# PWR_BUCK.net
KiCad netlist of a schematic drawn in Altium Designer
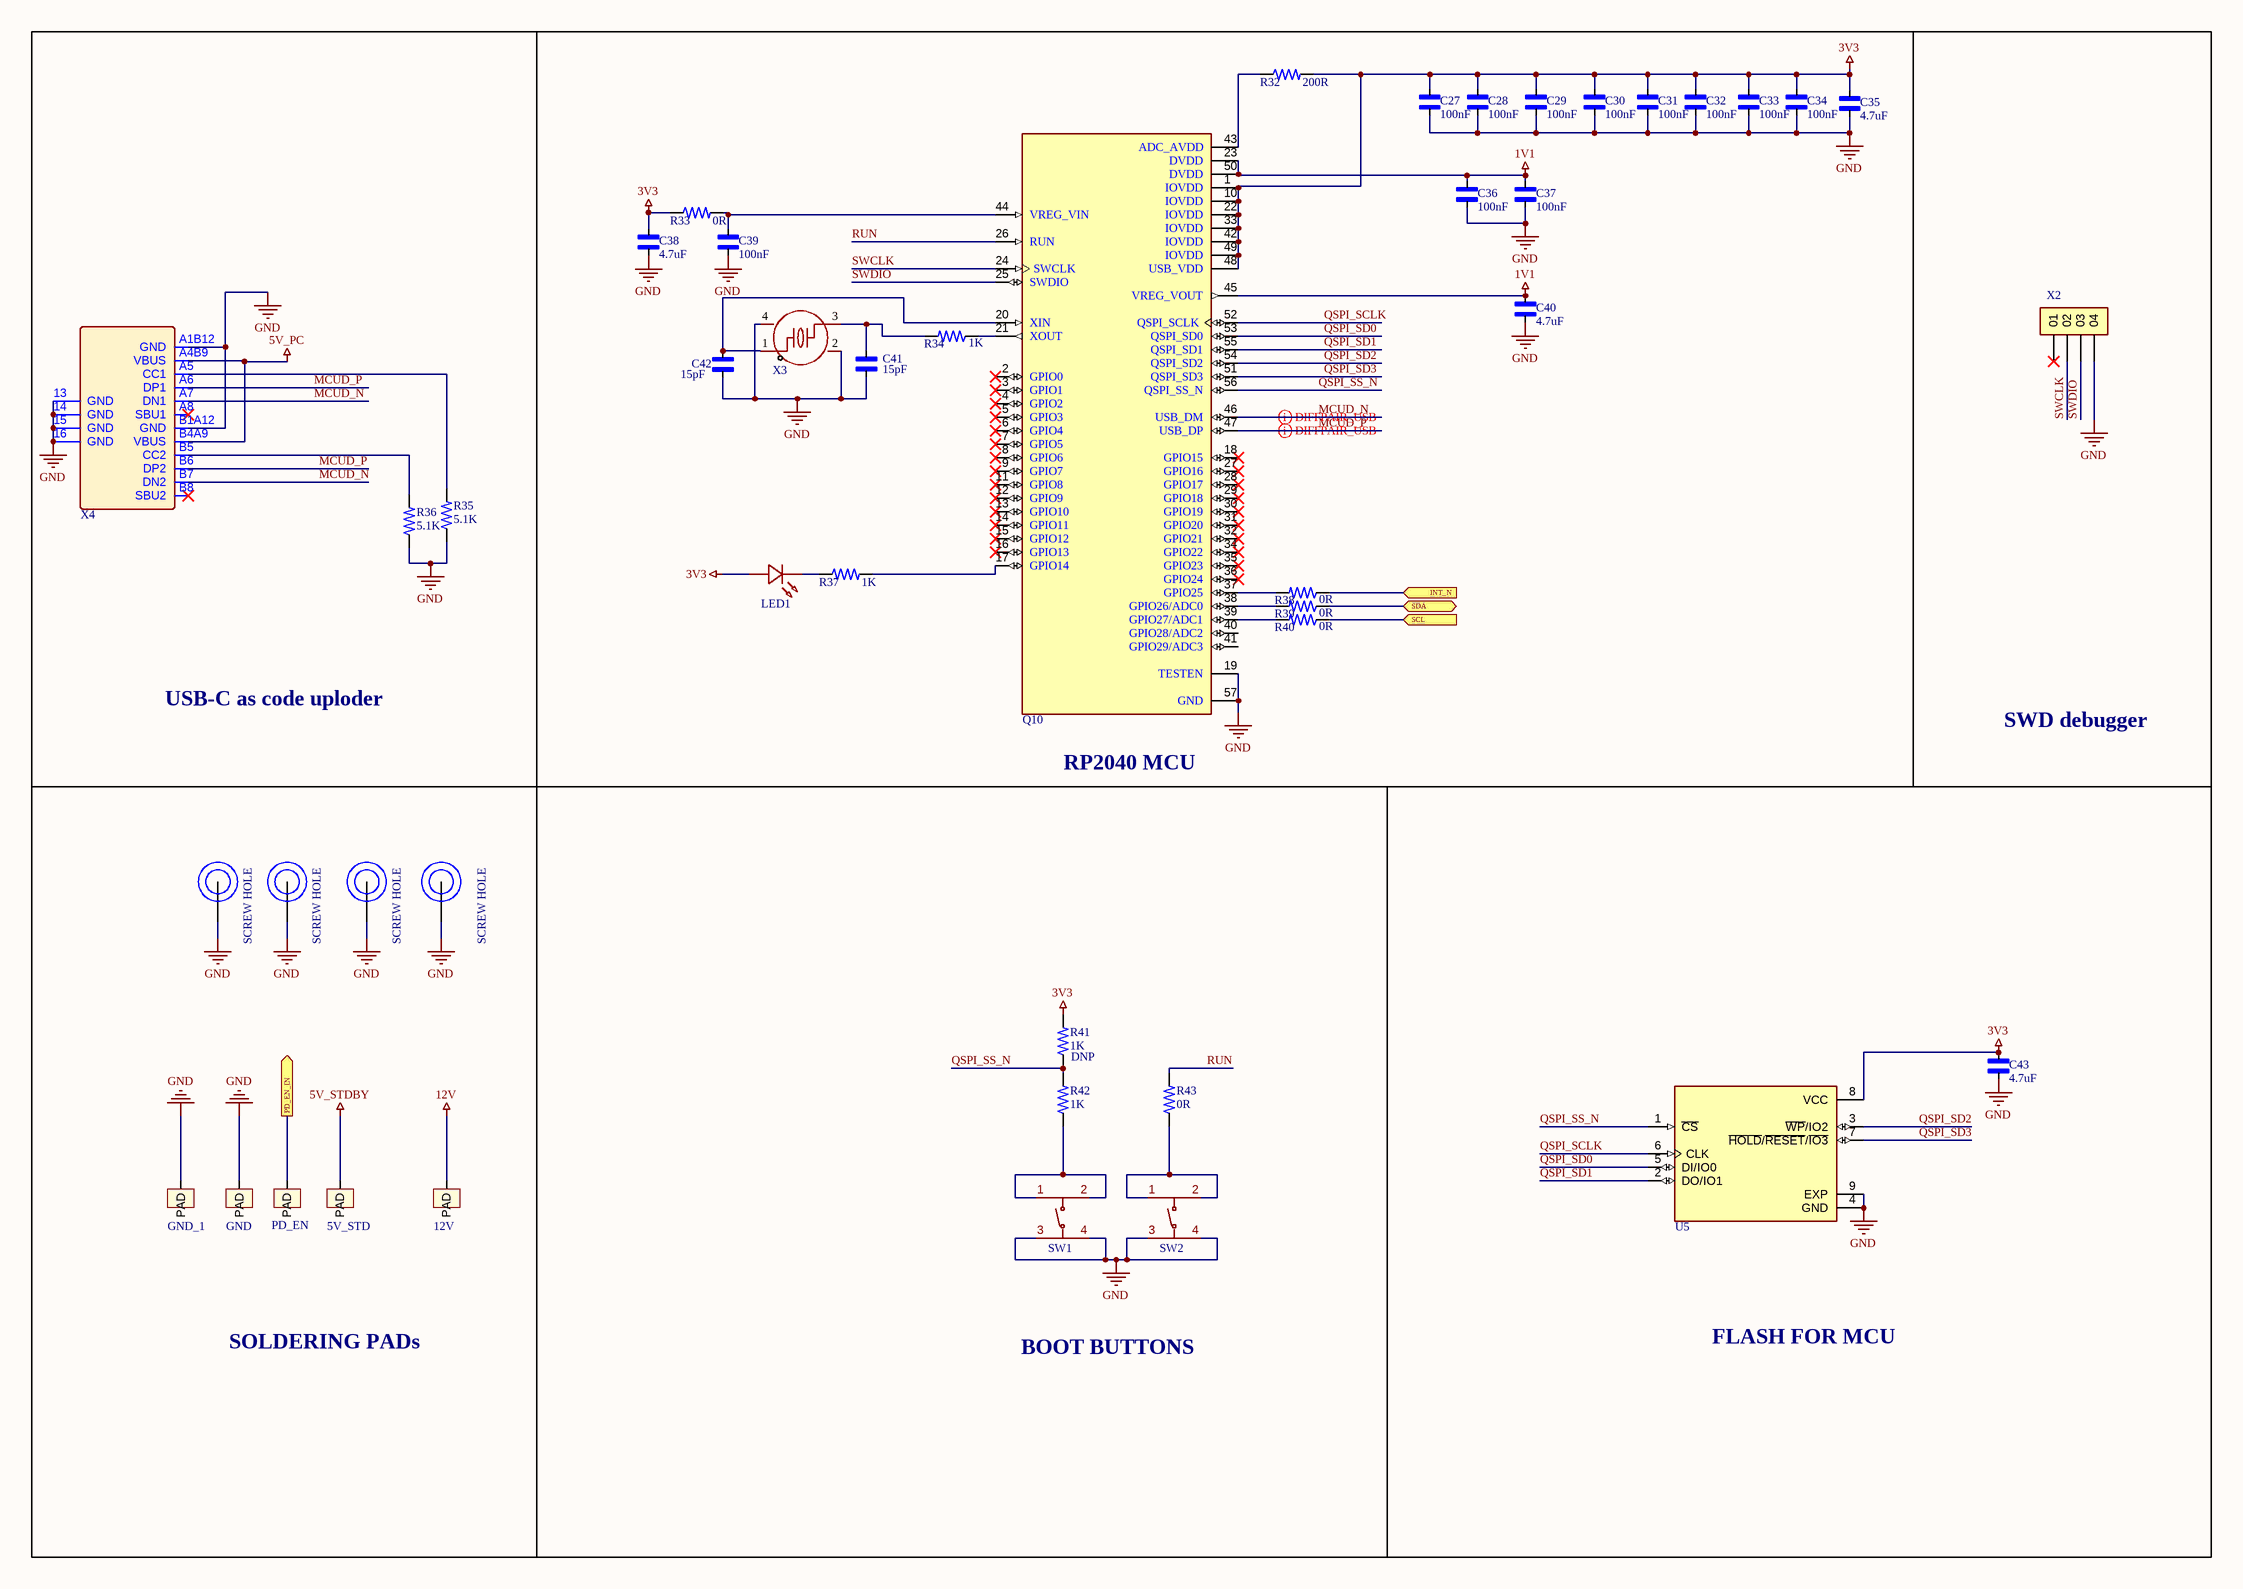
[diagram p0: PWR_BUCK.SchDoc]

(export (version "E")
  (design (tool "Eeschema 10.0.6"))
  (components
    (comp (ref "5V_STD")
      (value "solder pad")
      (footprint "1mm hole")
      (libsource (lib "USB_PD_PSU") (part "solder pad"))
    )
    (comp (ref "12V")
      (value "solder pad")
      (footprint "14 awg")
      (libsource (lib "USB_PD_PSU") (part "solder pad"))
    )
    (comp (ref "C27")
      (value "100nF")
      (footprint "CAP_0603")
      (description "SMD Capacitor")
      (fields (field (name "TOLERANCE") "±10%") (field (name "Comment") "SMD capacitor"))
      (libsource (lib "USB_PD_PSU") (part "CAP_SMD_CERAMIC"))
    )
    (comp (ref "C28")
      (value "100nF")
      (footprint "CAP_0603")
      (description "SMD Capacitor")
      (fields (field (name "TOLERANCE") "±10%") (field (name "Comment") "SMD capacitor"))
      (libsource (lib "USB_PD_PSU") (part "CAP_SMD_CERAMIC"))
    )
    (comp (ref "C29")
      (value "100nF")
      (footprint "CAP_0603")
      (description "SMD Capacitor")
      (fields (field (name "TOLERANCE") "±10%") (field (name "Comment") "SMD capacitor"))
      (libsource (lib "USB_PD_PSU") (part "CAP_SMD_CERAMIC"))
    )
    (comp (ref "C30")
      (value "100nF")
      (footprint "CAP_0603")
      (description "SMD Capacitor")
      (fields (field (name "TOLERANCE") "±10%") (field (name "Comment") "SMD capacitor"))
      (libsource (lib "USB_PD_PSU") (part "CAP_SMD_CERAMIC"))
    )
    (comp (ref "C31")
      (value "100nF")
      (footprint "CAP_0603")
      (description "SMD Capacitor")
      (fields (field (name "TOLERANCE") "±10%") (field (name "Comment") "SMD capacitor"))
      (libsource (lib "USB_PD_PSU") (part "CAP_SMD_CERAMIC"))
    )
    (comp (ref "C32")
      (value "100nF")
      (footprint "CAP_0603")
      (description "SMD Capacitor")
      (fields (field (name "TOLERANCE") "±10%") (field (name "Comment") "SMD capacitor"))
      (libsource (lib "USB_PD_PSU") (part "CAP_SMD_CERAMIC"))
    )
    (comp (ref "C33")
      (value "100nF")
      (footprint "CAP_0603")
      (description "SMD Capacitor")
      (fields (field (name "TOLERANCE") "±10%") (field (name "Comment") "SMD capacitor"))
      (libsource (lib "USB_PD_PSU") (part "CAP_SMD_CERAMIC"))
    )
    (comp (ref "C34")
      (value "100nF")
      (footprint "CAP_0603")
      (description "SMD Capacitor")
      (fields (field (name "TOLERANCE") "±10%") (field (name "Comment") "SMD capacitor"))
      (libsource (lib "USB_PD_PSU") (part "CAP_SMD_CERAMIC"))
    )
    (comp (ref "C35")
      (value "4.7uF")
      (footprint "CAP_0603")
      (description "SMD Capacitor")
      (fields (field (name "TOLERANCE") "±10%") (field (name "Comment") "SMD capacitor"))
      (libsource (lib "USB_PD_PSU") (part "CAP_SMD_CERAMIC"))
    )
    (comp (ref "C36")
      (value "100nF")
      (footprint "CAP_0603")
      (description "SMD Capacitor")
      (fields (field (name "TOLERANCE") "±10%") (field (name "Comment") "SMD capacitor"))
      (libsource (lib "USB_PD_PSU") (part "CAP_SMD_CERAMIC"))
    )
    (comp (ref "C37")
      (value "100nF")
      (footprint "CAP_0603")
      (description "SMD Capacitor")
      (fields (field (name "TOLERANCE") "±10%") (field (name "Comment") "SMD capacitor"))
      (libsource (lib "USB_PD_PSU") (part "CAP_SMD_CERAMIC"))
    )
    (comp (ref "C38")
      (value "4.7uF")
      (footprint "CAP_0603")
      (description "SMD Capacitor")
      (fields (field (name "TOLERANCE") "±10%") (field (name "Comment") "SMD capacitor"))
      (libsource (lib "USB_PD_PSU") (part "CAP_SMD_CERAMIC"))
    )
    (comp (ref "C39")
      (value "100nF")
      (footprint "CAP_0603")
      (description "SMD Capacitor")
      (fields (field (name "TOLERANCE") "±10%") (field (name "Comment") "SMD capacitor"))
      (libsource (lib "USB_PD_PSU") (part "CAP_SMD_CERAMIC"))
    )
    (comp (ref "C40")
      (value "4.7uF")
      (footprint "CAP_0603")
      (description "SMD Capacitor")
      (fields (field (name "TOLERANCE") "±10%") (field (name "Comment") "SMD capacitor"))
      (libsource (lib "USB_PD_PSU") (part "CAP_SMD_CERAMIC"))
    )
    (comp (ref "C41")
      (value "15pF")
      (footprint "CAP_0603")
      (description "SMD Capacitor")
      (fields (field (name "TOLERANCE") "±10%") (field (name "Comment") "SMD capacitor"))
      (libsource (lib "") (part "CAP_SMD_CERAMIC_1"))
    )
    (comp (ref "C42")
      (value "15pF")
      (footprint "CAP_0603")
      (description "SMD Capacitor")
      (fields (field (name "TOLERANCE") "±10%") (field (name "Comment") "SMD capacitor"))
      (libsource (lib "") (part "CAP_SMD_CERAMIC_1"))
    )
    (comp (ref "C43")
      (value "4.7uF")
      (footprint "CAP_0603")
      (description "SMD Capacitor")
      (fields (field (name "TOLERANCE") "±10%") (field (name "Comment") "SMD capacitor"))
      (libsource (lib "USB_PD_PSU") (part "CAP_SMD_CERAMIC"))
    )
    (comp (ref "GND")
      (value "solder pad")
      (footprint "14 awg")
      (libsource (lib "USB_PD_PSU") (part "solder pad"))
    )
    (comp (ref "GND_1")
      (value "solder pad")
      (footprint "1mm hole")
      (libsource (lib "USB_PD_PSU") (part "solder pad"))
    )
    (comp (ref "LED1")
      (value "LED")
      (footprint "LED0603-RD_RED")
      (description "LED  SMD")
      (fields (field (name "MANIFACTURING PART NUMBER") "SZYY0603O"))
      (libsource (lib "USB_PD_PSU") (part "LED SMD"))
    )
    (comp (ref "PD_EN")
      (value "solder pad")
      (footprint "1mm hole")
      (libsource (lib "USB_PD_PSU") (part "solder pad"))
    )
    (comp (ref "Q10")
      (value "IC MCU 32BIT EXT MEM 56QFN")
      (footprint "QFN40P700X700X90-57N")
      (description "ARM® Cortex®-M0+ - Microcontroller IC 32-Bit Dual-Core 133MHz External Program Memory 56-QFN (7x7)")
      (fields (field (name "MANIFACTURING PART NUMBER") "RP2040") (field (name "JLCPCB PART #") "C2040"))
      (libsource (lib "USB_PD_PSU") (part "RP2040"))
    )
    (comp (ref "R32")
      (value "200R")
      (footprint "RES_0603")
      (description "SMD Resistor")
      (fields (field (name "TOLERANCE") "±5%"))
      (libsource (lib "USB_PD_PSU") (part "RES_SMD_CERAMIC"))
    )
    (comp (ref "R33")
      (value "0R")
      (footprint "RES_0603")
      (description "SMD Resistor")
      (fields (field (name "TOLERANCE") "±5%"))
      (libsource (lib "USB_PD_PSU") (part "RES_SMD_CERAMIC"))
    )
    (comp (ref "R34")
      (value "1K")
      (footprint "RES_0603")
      (description "SMD Resistor")
      (fields (field (name "TOLERANCE") "±5%") (field (name "Comment") "SMD resistor"))
      (libsource (lib "USB_PD_PSU") (part "RES_SMD_CERAMIC"))
    )
    (comp (ref "R35")
      (value "5.1K")
      (footprint "RES_0603")
      (description "SMD Resistor")
      (fields (field (name "TOLERANCE") "±5%") (field (name "Comment") "SMD resistor"))
      (libsource (lib "USB_PD_PSU") (part "RES_SMD_CERAMIC"))
    )
    (comp (ref "R36")
      (value "5.1K")
      (footprint "RES_0603")
      (description "SMD Resistor")
      (fields (field (name "TOLERANCE") "±5%") (field (name "Comment") "SMD resistor"))
      (libsource (lib "USB_PD_PSU") (part "RES_SMD_CERAMIC"))
    )
    (comp (ref "R37")
      (value "1K")
      (footprint "RES_0603")
      (description "SMD Resistor")
      (fields (field (name "TOLERANCE") "±5%"))
      (libsource (lib "USB_PD_PSU") (part "RES_SMD_CERAMIC"))
    )
    (comp (ref "R38")
      (value "0R")
      (footprint "RES_0603")
      (description "SMD Resistor")
      (fields (field (name "TOLERANCE") "±5%") (field (name "Comment") "SMD resistor"))
      (libsource (lib "USB_PD_PSU") (part "RES_SMD_CERAMIC"))
    )
    (comp (ref "R39")
      (value "0R")
      (footprint "RES_0603")
      (description "SMD Resistor")
      (fields (field (name "TOLERANCE") "±5%") (field (name "Comment") "SMD resistor"))
      (libsource (lib "USB_PD_PSU") (part "RES_SMD_CERAMIC"))
    )
    (comp (ref "R40")
      (value "0R")
      (footprint "RES_0603")
      (description "SMD Resistor")
      (fields (field (name "TOLERANCE") "±5%") (field (name "Comment") "SMD resistor"))
      (libsource (lib "USB_PD_PSU") (part "RES_SMD_CERAMIC"))
    )
    (comp (ref "R41")
      (value "DNP")
      (footprint "RES_0603")
      (description "SMD Resistor")
      (fields (field (name "TOLERANCE") "±5%") (field (name "ALTIUM_VALUE") "1K"))
      (libsource (lib "USB_PD_PSU") (part "RES_SMD_CERAMIC"))
    )
    (comp (ref "R42")
      (value "1K")
      (footprint "RES_0603")
      (description "SMD Resistor")
      (fields (field (name "TOLERANCE") "±5%") (field (name "Comment") "SMD resistor"))
      (libsource (lib "USB_PD_PSU") (part "RES_SMD_CERAMIC"))
    )
    (comp (ref "R43")
      (value "0R")
      (footprint "RES_0603")
      (description "SMD Resistor")
      (fields (field (name "TOLERANCE") "±5%") (field (name "Comment") "SMD resistor"))
      (libsource (lib "USB_PD_PSU") (part "RES_SMD_CERAMIC"))
    )
    (comp (ref "SH1")
      (value "SCREW HOLE")
      (footprint "PCB hole")
      (libsource (lib "USB_PD_PSU") (part "Hole"))
    )
    (comp (ref "SH2")
      (value "SCREW HOLE")
      (footprint "PCB hole")
      (libsource (lib "USB_PD_PSU") (part "Hole"))
    )
    (comp (ref "SH3")
      (value "SCREW HOLE")
      (footprint "PCB hole")
      (libsource (lib "USB_PD_PSU") (part "Hole"))
    )
    (comp (ref "SH4")
      (value "SCREW HOLE")
      (footprint "PCB hole")
      (libsource (lib "USB_PD_PSU") (part "Hole"))
    )
    (comp (ref "SW1")
      (value "Dev  Switch")
      (footprint "SW-SMD_4P-L4.2-W3.3-P2.15-LS5.1")
      (description "50mA Brick nogging SPST 12V SMD,3.3x4.2mm Tactile Switches ROHS")
      (fields (field (name "MANIFACTURING PART NUMBER") "TS-1089S-02526") (field (name "TOLERANCE") "±5%"))
      (libsource (lib "USB_PD_PSU") (part "TS-1089S-02526"))
    )
    (comp (ref "SW2")
      (value "Dev  Switch")
      (footprint "SW-SMD_4P-L4.2-W3.3-P2.15-LS5.1")
      (description "50mA Brick nogging SPST 12V SMD,3.3x4.2mm Tactile Switches ROHS")
      (fields (field (name "MANIFACTURING PART NUMBER") "TS-1089S-02526") (field (name "TOLERANCE") "±5%"))
      (libsource (lib "USB_PD_PSU") (part "TS-1089S-02526"))
    )
    (comp (ref "U5")
      (value "SPI Flash")
      (footprint "IC_W25Q16JVUXIQ_TR")
      (description "16Mbit 2.7V~3.6V 133MHz SPI USON-8-EP(2x3) Memory (ICs) ROHS")
      (fields
        (field (name "MANIFACTURING PART NUMBER") "W25Q16JVUXIQ")
        (field (name "JLCPCB PART #") "C2843335")
      )
      (libsource (lib "USB_PD_PSU") (part "W25Q16JVUXIQ"))
    )
    (comp (ref "X2")
      (value "Header X 5")
      (footprint "SAMTEC_TS-104-T-A")
      (description "4 pin header pitch 2.54mm")
      (fields
        (field (name "MANIFACTURING PART NUMBER") "2541WV-04P")
        (field (name "JLCPCB PART #") "C5383113")
      )
      (libsource (lib "USB_PD_PSU") (part "4 Pin Header"))
    )
    (comp (ref "X3")
      (value "Crystals")
      (footprint "CRYSTAL-SMD_4P-L3.2-W2.5-BL")
      (description "12 MHz ±30ppm Crystal 10pF 50 Ohms 4-SMD, No Lead")
      (fields (field (name "MANIFACTURING PART NUMBER") "ABM8-272-T3") (field (name "TOLERANCE") "±30ppm"))
      (libsource (lib "USB_PD_PSU") (part "ABM8-272-T3"))
    )
    (comp (ref "X4")
      (value "USB-C connector")
      (footprint "USB-C-SMD_TYPEC-304J-BCP16")
      (description "5A USB 3.1 1 Surface Mount, Right Angle 16P Female -40℃~+85℃ Type-C SMD USB Connectors ROHS")
      (fields
        (field (name "MANIFACTURING PART NUMBER") "TYPEC-304J-BCP16")
        (field (name "JLCPCB PART #") "C2835315")
      )
      (libsource (lib "USB_PD_PSU") (part "TYPEC-304J-BCP16"))
    )
  )
  (nets
    (net (code "1") (name "/INT_N") (class "Default")
      (node (ref "R38") (pin "1") (pinfunction "1_1") (pintype "passive"))
    )
    (net (code "2") (name "/MCUD_N") (class "Default")
      (node (ref "Q10") (pin "46") (pinfunction "USB_DM_46") (pintype "bidirectional"))
      (node (ref "X4") (pin "A7") (pinfunction "DN1_A7") (pintype "passive"))
      (node (ref "X4") (pin "B7") (pinfunction "DN2_B7") (pintype "passive"))
    )
    (net (code "3") (name "/MCUD_P") (class "Default")
      (node (ref "Q10") (pin "47") (pinfunction "USB_DP_47") (pintype "bidirectional"))
      (node (ref "X4") (pin "A6") (pinfunction "DP1_A6") (pintype "passive"))
      (node (ref "X4") (pin "B6") (pinfunction "DP2_B6") (pintype "passive"))
    )
    (net (code "4") (name "/PD_EN_IN") (class "Default")
      (node (ref "PD_EN") (pin "1") (pinfunction "PAD_1") (pintype "passive"))
    )
    (net (code "5") (name "/QSPI_SCLK") (class "Default")
      (node (ref "Q10") (pin "52") (pinfunction "QSPI_SCLK_52") (pintype "bidirectional"))
      (node (ref "U5") (pin "6") (pinfunction "CLK_6") (pintype "input"))
    )
    (net (code "6") (name "/QSPI_SD0") (class "Default")
      (node (ref "Q10") (pin "53") (pinfunction "QSPI_SD0_53") (pintype "bidirectional"))
      (node (ref "U5") (pin "5") (pinfunction "DI/IO0_5") (pintype "bidirectional"))
    )
    (net (code "7") (name "/QSPI_SD1") (class "Default")
      (node (ref "Q10") (pin "55") (pinfunction "QSPI_SD1_55") (pintype "bidirectional"))
      (node (ref "U5") (pin "2") (pinfunction "DO/IO1_2") (pintype "bidirectional"))
    )
    (net (code "8") (name "/QSPI_SD2") (class "Default")
      (node (ref "Q10") (pin "54") (pinfunction "QSPI_SD2_54") (pintype "bidirectional"))
      (node (ref "U5") (pin "3") (pinfunction "~{WP}/IO2_3") (pintype "bidirectional"))
    )
    (net (code "9") (name "/QSPI_SD3") (class "Default")
      (node (ref "Q10") (pin "51") (pinfunction "QSPI_SD3_51") (pintype "bidirectional"))
      (node (ref "U5") (pin "7") (pinfunction "~{HOLD}/~{RESET}/~{IO3}_7") (pintype "bidirectional"))
    )
    (net (code "10") (name "/QSPI_SS_N") (class "Default")
      (node (ref "Q10") (pin "56") (pinfunction "QSPI_SS_N_56") (pintype "bidirectional"))
      (node (ref "R41") (pin "1") (pinfunction "1_1") (pintype "passive"))
      (node (ref "R42") (pin "2") (pinfunction "2_2") (pintype "passive"))
      (node (ref "U5") (pin "1") (pinfunction "~{CS}_1") (pintype "input"))
    )
    (net (code "11") (name "/RUN") (class "Default")
      (node (ref "Q10") (pin "26") (pinfunction "RUN_26") (pintype "input"))
      (node (ref "R43") (pin "2") (pinfunction "2_2") (pintype "passive"))
    )
    (net (code "12") (name "/SCL") (class "Default")
      (node (ref "R40") (pin "1") (pinfunction "1_1") (pintype "passive"))
    )
    (net (code "13") (name "/SDA") (class "Default")
      (node (ref "R39") (pin "1") (pinfunction "1_1") (pintype "passive"))
    )
    (net (code "14") (name "/SWCLK") (class "Default")
      (node (ref "Q10") (pin "24") (pinfunction "SWCLK_24") (pintype "input"))
      (node (ref "X2") (pin "02") (pinfunction "02_02") (pintype "passive"))
    )
    (net (code "15") (name "/SWDIO") (class "Default")
      (node (ref "Q10") (pin "25") (pinfunction "SWDIO_25") (pintype "bidirectional"))
      (node (ref "X2") (pin "03") (pinfunction "03_03") (pintype "passive"))
    )
    (net (code "16") (name "1V1") (class "Default")
      (node (ref "C36") (pin "1") (pinfunction "1_1") (pintype "passive"))
      (node (ref "C37") (pin "1") (pinfunction "1_1") (pintype "passive"))
      (node (ref "C40") (pin "1") (pinfunction "1_1") (pintype "passive"))
      (node (ref "Q10") (pin "23") (pinfunction "DVDD_23") (pintype "power_in"))
      (node (ref "Q10") (pin "45") (pinfunction "VREG_VOUT_45") (pintype "output"))
      (node (ref "Q10") (pin "50") (pinfunction "DVDD_50") (pintype "power_in"))
    )
    (net (code "17") (name "3V3") (class "Default")
      (node (ref "C27") (pin "1") (pinfunction "1_1") (pintype "passive"))
      (node (ref "C28") (pin "1") (pinfunction "1_1") (pintype "passive"))
      (node (ref "C29") (pin "1") (pinfunction "1_1") (pintype "passive"))
      (node (ref "C30") (pin "1") (pinfunction "1_1") (pintype "passive"))
      (node (ref "C31") (pin "1") (pinfunction "1_1") (pintype "passive"))
      (node (ref "C32") (pin "1") (pinfunction "1_1") (pintype "passive"))
      (node (ref "C33") (pin "1") (pinfunction "1_1") (pintype "passive"))
      (node (ref "C34") (pin "1") (pinfunction "1_1") (pintype "passive"))
      (node (ref "C35") (pin "1") (pinfunction "1_1") (pintype "passive"))
      (node (ref "C38") (pin "1") (pinfunction "1_1") (pintype "passive"))
      (node (ref "C43") (pin "1") (pinfunction "1_1") (pintype "passive"))
      (node (ref "LED1") (pin "2") (pinfunction "A_2") (pintype "passive"))
      (node (ref "Q10") (pin "1") (pinfunction "IOVDD_1") (pintype "power_in"))
      (node (ref "Q10") (pin "10") (pinfunction "IOVDD_10") (pintype "power_in"))
      (node (ref "Q10") (pin "22") (pinfunction "IOVDD_22") (pintype "power_in"))
      (node (ref "Q10") (pin "33") (pinfunction "IOVDD_33") (pintype "power_in"))
      (node (ref "Q10") (pin "42") (pinfunction "IOVDD_42") (pintype "power_in"))
      (node (ref "Q10") (pin "48") (pinfunction "USB_VDD_48") (pintype "power_in"))
      (node (ref "Q10") (pin "49") (pinfunction "IOVDD_49") (pintype "power_in"))
      (node (ref "R32") (pin "2") (pinfunction "2_2") (pintype "passive"))
      (node (ref "R33") (pin "1") (pinfunction "1_1") (pintype "passive"))
      (node (ref "R41") (pin "2") (pinfunction "2_2") (pintype "passive"))
      (node (ref "U5") (pin "8") (pinfunction "VCC_8") (pintype "power_in"))
    )
    (net (code "18") (name "5V_PC") (class "Default")
      (node (ref "X4") (pin "A4B9") (pinfunction "VBUS_A4B9") (pintype "passive"))
      (node (ref "X4") (pin "B4A9") (pinfunction "VBUS_B4A9") (pintype "passive"))
    )
    (net (code "19") (name "5V_STDBY") (class "Default")
      (node (ref "5V_STD") (pin "1") (pinfunction "PAD_1") (pintype "passive"))
    )
    (net (code "20") (name "12V") (class "Default")
      (node (ref "12V") (pin "1") (pinfunction "PAD_1") (pintype "passive"))
    )
    (net (code "21") (name "GND") (class "Default")
      (node (ref "C27") (pin "2") (pinfunction "2_2") (pintype "passive"))
      (node (ref "C28") (pin "2") (pinfunction "2_2") (pintype "passive"))
      (node (ref "C29") (pin "2") (pinfunction "2_2") (pintype "passive"))
      (node (ref "C30") (pin "2") (pinfunction "2_2") (pintype "passive"))
      (node (ref "C31") (pin "2") (pinfunction "2_2") (pintype "passive"))
      (node (ref "C32") (pin "2") (pinfunction "2_2") (pintype "passive"))
      (node (ref "C33") (pin "2") (pinfunction "2_2") (pintype "passive"))
      (node (ref "C34") (pin "2") (pinfunction "2_2") (pintype "passive"))
      (node (ref "C35") (pin "2") (pinfunction "2_2") (pintype "passive"))
      (node (ref "C36") (pin "2") (pinfunction "2_2") (pintype "passive"))
      (node (ref "C37") (pin "2") (pinfunction "2_2") (pintype "passive"))
      (node (ref "C38") (pin "2") (pinfunction "2_2") (pintype "passive"))
      (node (ref "C39") (pin "2") (pinfunction "2_2") (pintype "passive"))
      (node (ref "C40") (pin "2") (pinfunction "2_2") (pintype "passive"))
      (node (ref "C41") (pin "2") (pinfunction "2_2") (pintype "passive"))
      (node (ref "C42") (pin "2") (pinfunction "2_2") (pintype "passive"))
      (node (ref "C43") (pin "2") (pinfunction "2_2") (pintype "passive"))
      (node (ref "GND") (pin "1") (pinfunction "PAD_1") (pintype "passive"))
      (node (ref "GND_1") (pin "1") (pinfunction "PAD_1") (pintype "passive"))
      (node (ref "Q10") (pin "19") (pinfunction "TESTEN_19") (pintype "passive"))
      (node (ref "Q10") (pin "57") (pinfunction "GND_57") (pintype "power_in"))
      (node (ref "R35") (pin "1") (pinfunction "1_1") (pintype "passive"))
      (node (ref "R36") (pin "1") (pinfunction "1_1") (pintype "passive"))
      (node (ref "SH1") (pin "1") (pinfunction "1_1") (pintype "passive"))
      (node (ref "SH2") (pin "1") (pinfunction "1_1") (pintype "passive"))
      (node (ref "SH3") (pin "1") (pinfunction "1_1") (pintype "passive"))
      (node (ref "SH4") (pin "1") (pinfunction "1_1") (pintype "passive"))
      (node (ref "SW1") (pin "3") (pinfunction "3_3") (pintype "passive"))
      (node (ref "SW1") (pin "4") (pinfunction "4_4") (pintype "passive"))
      (node (ref "SW2") (pin "3") (pinfunction "3_3") (pintype "passive"))
      (node (ref "SW2") (pin "4") (pinfunction "4_4") (pintype "passive"))
      (node (ref "U5") (pin "4") (pinfunction "GND_4") (pintype "power_in"))
      (node (ref "U5") (pin "9") (pinfunction "EXP_9") (pintype "passive"))
      (node (ref "X2") (pin "04") (pinfunction "04_04") (pintype "passive"))
      (node (ref "X3") (pin "2") (pinfunction "GND_2") (pintype "passive"))
      (node (ref "X3") (pin "4") (pinfunction "GND_4") (pintype "passive"))
      (node (ref "X4") (pin "13") (pinfunction "GND_13") (pintype "passive"))
      (node (ref "X4") (pin "14") (pinfunction "GND_14") (pintype "passive"))
      (node (ref "X4") (pin "15") (pinfunction "GND_15") (pintype "passive"))
      (node (ref "X4") (pin "16") (pinfunction "GND_16") (pintype "passive"))
      (node (ref "X4") (pin "A1B12") (pinfunction "GND_A1B12") (pintype "passive"))
      (node (ref "X4") (pin "B1A12") (pinfunction "GND_B1A12") (pintype "passive"))
    )
    (net (code "22") (name "Net-(C41-Pad1)") (class "Default")
      (node (ref "C41") (pin "1") (pinfunction "1_1") (pintype "passive"))
      (node (ref "R34") (pin "2") (pinfunction "2_2") (pintype "passive"))
      (node (ref "X3") (pin "3") (pinfunction "3_3") (pintype "passive"))
    )
    (net (code "23") (name "Net-(LED1-K)") (class "Default")
      (node (ref "LED1") (pin "1") (pinfunction "K_1") (pintype "passive"))
      (node (ref "R37") (pin "1") (pinfunction "1_1") (pintype "passive"))
    )
    (net (code "24") (name "Net-(Q10-ADC_AVDD)") (class "Default")
      (node (ref "Q10") (pin "43") (pinfunction "ADC_AVDD_43") (pintype "power_in"))
      (node (ref "R32") (pin "1") (pinfunction "1_1") (pintype "passive"))
    )
    (net (code "25") (name "Net-(Q10-GPIO14)") (class "Default")
      (node (ref "Q10") (pin "17") (pinfunction "GPIO14_17") (pintype "bidirectional"))
      (node (ref "R37") (pin "2") (pinfunction "2_2") (pintype "passive"))
    )
    (net (code "26") (name "Net-(Q10-GPIO25)") (class "Default")
      (node (ref "Q10") (pin "37") (pinfunction "GPIO25_37") (pintype "bidirectional"))
      (node (ref "R38") (pin "2") (pinfunction "2_2") (pintype "passive"))
    )
    (net (code "27") (name "Net-(Q10-GPIO26{slash}ADC0)") (class "Default")
      (node (ref "Q10") (pin "38") (pinfunction "GPIO26/ADC0_38") (pintype "bidirectional"))
      (node (ref "R39") (pin "2") (pinfunction "2_2") (pintype "passive"))
    )
    (net (code "28") (name "Net-(Q10-GPIO27{slash}ADC1)") (class "Default")
      (node (ref "Q10") (pin "39") (pinfunction "GPIO27/ADC1_39") (pintype "bidirectional"))
      (node (ref "R40") (pin "2") (pinfunction "2_2") (pintype "passive"))
    )
    (net (code "29") (name "Net-(Q10-VREG_VIN)") (class "Default")
      (node (ref "C39") (pin "1") (pinfunction "1_1") (pintype "passive"))
      (node (ref "Q10") (pin "44") (pinfunction "VREG_VIN_44") (pintype "input"))
      (node (ref "R33") (pin "2") (pinfunction "2_2") (pintype "passive"))
    )
    (net (code "30") (name "Net-(Q10-XIN)") (class "Default")
      (node (ref "C42") (pin "1") (pinfunction "1_1") (pintype "passive"))
      (node (ref "Q10") (pin "20") (pinfunction "XIN_20") (pintype "input"))
      (node (ref "X3") (pin "1") (pinfunction "1_1") (pintype "passive"))
    )
    (net (code "31") (name "Net-(Q10-XOUT)") (class "Default")
      (node (ref "Q10") (pin "21") (pinfunction "XOUT_21") (pintype "output"))
      (node (ref "R34") (pin "1") (pinfunction "1_1") (pintype "passive"))
    )
    (net (code "32") (name "Net-(R42-Pad1)") (class "Default")
      (node (ref "R42") (pin "1") (pinfunction "1_1") (pintype "passive"))
      (node (ref "SW1") (pin "1") (pinfunction "1_1") (pintype "passive"))
      (node (ref "SW1") (pin "2") (pinfunction "2_2") (pintype "passive"))
    )
    (net (code "33") (name "Net-(R43-Pad1)") (class "Default")
      (node (ref "R43") (pin "1") (pinfunction "1_1") (pintype "passive"))
      (node (ref "SW2") (pin "1") (pinfunction "1_1") (pintype "passive"))
      (node (ref "SW2") (pin "2") (pinfunction "2_2") (pintype "passive"))
    )
    (net (code "34") (name "Net-(X4-CC1)") (class "Default")
      (node (ref "R35") (pin "2") (pinfunction "2_2") (pintype "passive"))
      (node (ref "X4") (pin "A5") (pinfunction "CC1_A5") (pintype "passive"))
    )
    (net (code "35") (name "Net-(X4-CC2)") (class "Default")
      (node (ref "R36") (pin "2") (pinfunction "2_2") (pintype "passive"))
      (node (ref "X4") (pin "B5") (pinfunction "CC2_B5") (pintype "passive"))
    )
    (net (code "36") (name "unconnected-(Q10-GPIO0-Pad2)") (class "Default")
      (node (ref "Q10") (pin "2") (pinfunction "GPIO0_2") (pintype "bidirectional+no_connect"))
    )
    (net (code "37") (name "unconnected-(Q10-GPIO1-Pad3)") (class "Default")
      (node (ref "Q10") (pin "3") (pinfunction "GPIO1_3") (pintype "bidirectional+no_connect"))
    )
    (net (code "38") (name "unconnected-(Q10-GPIO2-Pad4)") (class "Default")
      (node (ref "Q10") (pin "4") (pinfunction "GPIO2_4") (pintype "bidirectional+no_connect"))
    )
    (net (code "39") (name "unconnected-(Q10-GPIO3-Pad5)") (class "Default")
      (node (ref "Q10") (pin "5") (pinfunction "GPIO3_5") (pintype "bidirectional+no_connect"))
    )
    (net (code "40") (name "unconnected-(Q10-GPIO4-Pad6)") (class "Default")
      (node (ref "Q10") (pin "6") (pinfunction "GPIO4_6") (pintype "bidirectional+no_connect"))
    )
    (net (code "41") (name "unconnected-(Q10-GPIO5-Pad7)") (class "Default")
      (node (ref "Q10") (pin "7") (pinfunction "GPIO5_7") (pintype "bidirectional+no_connect"))
    )
    (net (code "42") (name "unconnected-(Q10-GPIO6-Pad8)") (class "Default")
      (node (ref "Q10") (pin "8") (pinfunction "GPIO6_8") (pintype "bidirectional+no_connect"))
    )
    (net (code "43") (name "unconnected-(Q10-GPIO7-Pad9)") (class "Default")
      (node (ref "Q10") (pin "9") (pinfunction "GPIO7_9") (pintype "bidirectional+no_connect"))
    )
    (net (code "44") (name "unconnected-(Q10-GPIO8-Pad11)") (class "Default")
      (node (ref "Q10") (pin "11") (pinfunction "GPIO8_11") (pintype "bidirectional+no_connect"))
    )
    (net (code "45") (name "unconnected-(Q10-GPIO9-Pad12)") (class "Default")
      (node (ref "Q10") (pin "12") (pinfunction "GPIO9_12") (pintype "bidirectional+no_connect"))
    )
    (net (code "46") (name "unconnected-(Q10-GPIO10-Pad13)") (class "Default")
      (node (ref "Q10") (pin "13") (pinfunction "GPIO10_13") (pintype "bidirectional+no_connect"))
    )
    (net (code "47") (name "unconnected-(Q10-GPIO11-Pad14)") (class "Default")
      (node (ref "Q10") (pin "14") (pinfunction "GPIO11_14") (pintype "bidirectional+no_connect"))
    )
    (net (code "48") (name "unconnected-(Q10-GPIO12-Pad15)") (class "Default")
      (node (ref "Q10") (pin "15") (pinfunction "GPIO12_15") (pintype "bidirectional+no_connect"))
    )
    (net (code "49") (name "unconnected-(Q10-GPIO13-Pad16)") (class "Default")
      (node (ref "Q10") (pin "16") (pinfunction "GPIO13_16") (pintype "bidirectional+no_connect"))
    )
    (net (code "50") (name "unconnected-(Q10-GPIO15-Pad18)") (class "Default")
      (node (ref "Q10") (pin "18") (pinfunction "GPIO15_18") (pintype "bidirectional+no_connect"))
    )
    (net (code "51") (name "unconnected-(Q10-GPIO16-Pad27)") (class "Default")
      (node (ref "Q10") (pin "27") (pinfunction "GPIO16_27") (pintype "bidirectional+no_connect"))
    )
    (net (code "52") (name "unconnected-(Q10-GPIO17-Pad28)") (class "Default")
      (node (ref "Q10") (pin "28") (pinfunction "GPIO17_28") (pintype "bidirectional+no_connect"))
    )
    (net (code "53") (name "unconnected-(Q10-GPIO18-Pad29)") (class "Default")
      (node (ref "Q10") (pin "29") (pinfunction "GPIO18_29") (pintype "bidirectional+no_connect"))
    )
    (net (code "54") (name "unconnected-(Q10-GPIO19-Pad30)") (class "Default")
      (node (ref "Q10") (pin "30") (pinfunction "GPIO19_30") (pintype "bidirectional+no_connect"))
    )
    (net (code "55") (name "unconnected-(Q10-GPIO20-Pad31)") (class "Default")
      (node (ref "Q10") (pin "31") (pinfunction "GPIO20_31") (pintype "bidirectional+no_connect"))
    )
    (net (code "56") (name "unconnected-(Q10-GPIO21-Pad32)") (class "Default")
      (node (ref "Q10") (pin "32") (pinfunction "GPIO21_32") (pintype "bidirectional+no_connect"))
    )
    (net (code "57") (name "unconnected-(Q10-GPIO22-Pad34)") (class "Default")
      (node (ref "Q10") (pin "34") (pinfunction "GPIO22_34") (pintype "bidirectional+no_connect"))
    )
    (net (code "58") (name "unconnected-(Q10-GPIO23-Pad35)") (class "Default")
      (node (ref "Q10") (pin "35") (pinfunction "GPIO23_35") (pintype "bidirectional+no_connect"))
    )
    (net (code "59") (name "unconnected-(Q10-GPIO24-Pad36)") (class "Default")
      (node (ref "Q10") (pin "36") (pinfunction "GPIO24_36") (pintype "bidirectional+no_connect"))
    )
    (net (code "60") (name "unconnected-(Q10-GPIO28{slash}ADC2-Pad40)") (class "Default")
      (node (ref "Q10") (pin "40") (pinfunction "GPIO28/ADC2_40") (pintype "bidirectional"))
    )
    (net (code "61") (name "unconnected-(Q10-GPIO29{slash}ADC3-Pad41)") (class "Default")
      (node (ref "Q10") (pin "41") (pinfunction "GPIO29/ADC3_41") (pintype "bidirectional"))
    )
    (net (code "62") (name "unconnected-(X2-Pad01)") (class "Default")
      (node (ref "X2") (pin "01") (pinfunction "01_01") (pintype "passive+no_connect"))
    )
    (net (code "63") (name "unconnected-(X4-SBU1-PadA8)") (class "Default")
      (node (ref "X4") (pin "A8") (pinfunction "SBU1_A8") (pintype "passive+no_connect"))
    )
    (net (code "64") (name "unconnected-(X4-SBU2-PadB8)") (class "Default")
      (node (ref "X4") (pin "B8") (pinfunction "SBU2_B8") (pintype "passive+no_connect"))
    )
  )
)
